# LLCC68.net
KiCad netlist of a schematic drawn in Altium Designer
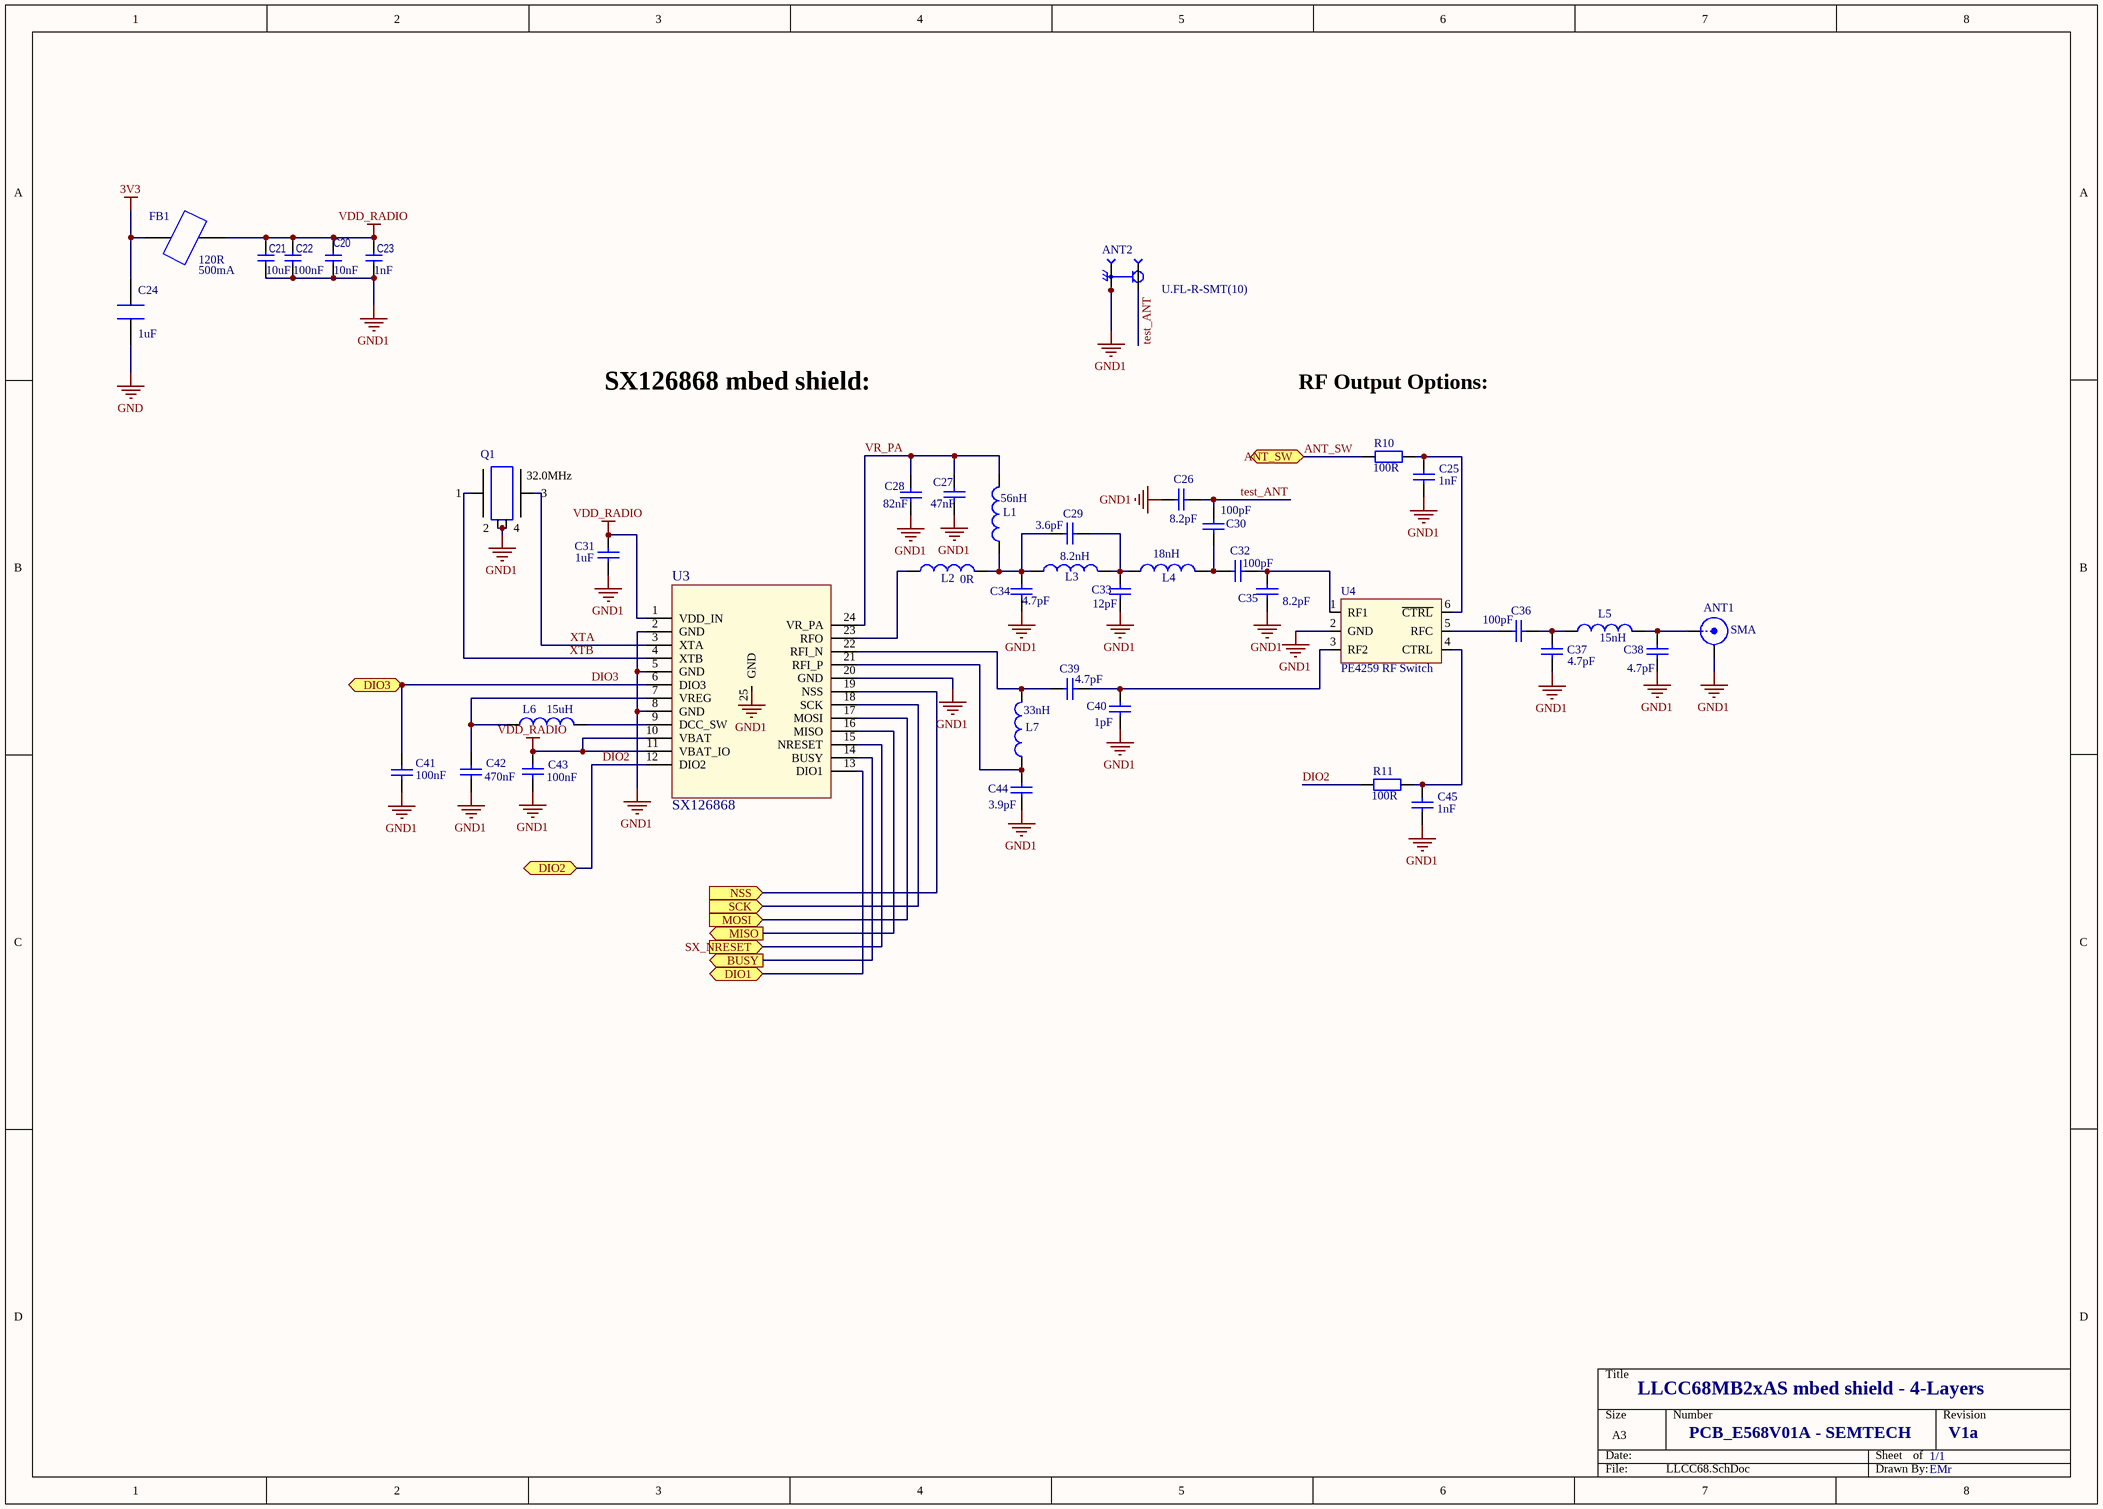
[diagram p0: LLCC68.SchDoc]

(export (version "E")
  (design (tool "Eeschema 10.0.6"))
  (components
    (comp (ref "ANT1")
      (value "SMA")
      (footprint "SMA_end_launch_1.0mm_9.52mm")
      (description "SMA Straight Connector")
      (fields (field (name "PUBLISHER") "Altium Limited"))
      (libsource (lib "SX1262MB2xAS_e499v01b") (part "SMA"))
    )
    (comp (ref "ANT2")
      (value "U.FL-R-SMT(10)")
      (footprint "HRS_U.FL-R-SMT(10)")
      (description "U.FL _UMCC_ Connector Receptacle, Male Pin 50Ohm Surface Mount Solder")
      (fields (field (name "MP") "U.FL-R-SMT_10_") (field (name "MF") "Hirose"))
      (libsource (lib "baseboard") (part "U.FL-R-SMT(10)"))
    )
    (comp (ref "C20")
      (value "10nF")
      (footprint "rlc_402_smd")
      (libsource (lib "baseboard") (part "ProE.tmp_22p_13"))
    )
    (comp (ref "C21")
      (value "10uF")
      (footprint "rlc_402_smd")
      (libsource (lib "baseboard") (part "ProE.tmp_22p_13"))
    )
    (comp (ref "C22")
      (value "100nF")
      (footprint "rlc_402_smd")
      (libsource (lib "baseboard") (part "ProE.tmp_22p_13"))
    )
    (comp (ref "C23")
      (value "1nF")
      (footprint "rlc_402_smd")
      (libsource (lib "baseboard") (part "ProE.tmp_22p_13"))
    )
    (comp (ref "C24")
      (value "1uF")
      (footprint "rlc_402_smd")
      (description "MLCC 4.7uF 0805 X5R 10V")
      (fields
        (field (name "XMOS PART NUMBER") "E-02-0021")
        (field (name "MANUFACTURER") "Murata")
        (field (name "PART CREATOR") "JG")
        (field (name "APPROVED") "NO")
      )
      (libsource (lib "XMOS_Alt_Lib") (part "CAP_NP"))
    )
    (comp (ref "C25")
      (value "1nF")
      (footprint "rlc_402_smd")
      (description "Capacitor SMD")
      (fields (field (name "PUBLISHER") "Altium Limited"))
      (libsource (lib "SX1262MB2xAS_e499v01b") (part "Cap"))
    )
    (comp (ref "C26")
      (value "8.2pF")
      (footprint "rlc_402_smd")
      (description "Capacitor SMD")
      (fields (field (name "PUBLISHER") "Altium Limited"))
      (libsource (lib "SX1262MB2xAS_e499v01b") (part "Cap"))
    )
    (comp (ref "C27")
      (value "47nF")
      (footprint "rlc_402_smd")
      (description "Capacitor SMD")
      (fields (field (name "PUBLISHER") "Altium Limited"))
      (libsource (lib "SX1262MB2xAS_e499v01b") (part "Cap"))
    )
    (comp (ref "C28")
      (value "82nF")
      (footprint "rlc_402_smd")
      (description "Capacitor SMD")
      (fields (field (name "PUBLISHER") "Altium Limited"))
      (libsource (lib "SX1262MB2xAS_e499v01b") (part "Cap"))
    )
    (comp (ref "C29")
      (value "3.6pF")
      (footprint "rlc_402_smd")
      (description "Capacitor SMD")
      (fields (field (name "PUBLISHER") "Altium Limited"))
      (libsource (lib "SX1262MB2xAS_e499v01b") (part "Cap"))
    )
    (comp (ref "C30")
      (value "100pF")
      (footprint "rlc_402_smd")
      (description "Capacitor SMD")
      (fields (field (name "PUBLISHER") "Altium Limited"))
      (libsource (lib "SX1262MB2xAS_e499v01b") (part "Cap"))
    )
    (comp (ref "C31")
      (value "1uF")
      (footprint "rlc_402_smd")
      (description "Capacitor SMD")
      (fields (field (name "PUBLISHER") "Altium Limited"))
      (libsource (lib "SX1262MB2xAS_e499v01b") (part "Cap"))
    )
    (comp (ref "C32")
      (value "100pF")
      (footprint "rlc_402_smd")
      (description "Capacitor SMD")
      (fields (field (name "PUBLISHER") "Altium Limited"))
      (libsource (lib "SX1262MB2xAS_e499v01b") (part "Cap"))
    )
    (comp (ref "C33")
      (value "12pF")
      (footprint "rlc_402_smd")
      (description "Capacitor SMD")
      (fields (field (name "PUBLISHER") "Altium Limited"))
      (libsource (lib "SX1262MB2xAS_e499v01b") (part "Cap"))
    )
    (comp (ref "C34")
      (value "4.7pF")
      (footprint "rlc_402_smd")
      (description "Capacitor SMD")
      (fields (field (name "PUBLISHER") "Altium Limited"))
      (libsource (lib "SX1262MB2xAS_e499v01b") (part "Cap"))
    )
    (comp (ref "C35")
      (value "8.2pF")
      (footprint "rlc_402_smd")
      (description "Capacitor SMD")
      (fields (field (name "PUBLISHER") "Altium Limited"))
      (libsource (lib "SX1262MB2xAS_e499v01b") (part "Cap"))
    )
    (comp (ref "C36")
      (value "100pF")
      (footprint "rlc_402_smd")
      (description "Capacitor SMD")
      (fields (field (name "PUBLISHER") "Altium Limited"))
      (libsource (lib "SX1262MB2xAS_e499v01b") (part "Cap"))
    )
    (comp (ref "C37")
      (value "4.7pF")
      (footprint "rlc_402_smd")
      (description "Capacitor SMD")
      (fields (field (name "PUBLISHER") "Altium Limited"))
      (libsource (lib "SX1262MB2xAS_e499v01b") (part "Cap"))
    )
    (comp (ref "C38")
      (value "4.7pF")
      (footprint "rlc_402_smd")
      (description "Capacitor SMD")
      (fields (field (name "PUBLISHER") "Altium Limited"))
      (libsource (lib "SX1262MB2xAS_e499v01b") (part "Cap"))
    )
    (comp (ref "C39")
      (value "4.7pF")
      (footprint "rlc_402_smd")
      (description "Capacitor SMD")
      (fields (field (name "PUBLISHER") "Altium Limited"))
      (libsource (lib "SX1262MB2xAS_e499v01b") (part "Cap"))
    )
    (comp (ref "C40")
      (value "1pF")
      (footprint "rlc_402_smd")
      (description "Capacitor SMD")
      (fields (field (name "PUBLISHER") "Altium Limited"))
      (libsource (lib "SX1262MB2xAS_e499v01b") (part "Cap"))
    )
    (comp (ref "C41")
      (value "100nF")
      (footprint "rlc_402_smd")
      (description "Capacitor SMD")
      (fields (field (name "PUBLISHER") "Altium Limited"))
      (libsource (lib "LLCC68MB2xAS_e568v01a") (part "Cap"))
    )
    (comp (ref "C42")
      (value "470nF")
      (footprint "rlc_402_smd")
      (description "Capacitor SMD")
      (fields (field (name "PUBLISHER") "Altium Limited"))
      (libsource (lib "SX1262MB2xAS_e499v01b") (part "Cap"))
    )
    (comp (ref "C43")
      (value "100nF")
      (footprint "rlc_402_smd")
      (description "Capacitor SMD")
      (fields (field (name "PUBLISHER") "Altium Limited"))
      (libsource (lib "SX1262MB2xAS_e499v01b") (part "Cap"))
    )
    (comp (ref "C44")
      (value "3.9pF")
      (footprint "rlc_402_smd")
      (description "Capacitor SMD")
      (fields (field (name "PUBLISHER") "Altium Limited"))
      (libsource (lib "SX1262MB2xAS_e499v01b") (part "Cap"))
    )
    (comp (ref "C45")
      (value "1nF")
      (footprint "rlc_402_smd")
      (description "Capacitor SMD")
      (fields (field (name "PUBLISHER") "Altium Limited"))
      (libsource (lib "SX1262MB2xAS_e499v01b") (part "Cap"))
    )
    (comp (ref "FB1")
      (value "120R")
      (footprint "R0603")
      (description "Ferrite Bead, 120R AT 100MHz, 0603, 500mA")
      (fields
        (field (name "XMOS PART NUMBER") "E-08-0007")
        (field (name "RATED CURRENT") "500mA")
        (field (name "MANUFACTURER") "Murata")
        (field (name "PART CREATOR") "JG")
        (field (name "APPROVED") "NO")
      )
      (libsource (lib "XMOS_Alt_Lib") (part "FERRITE"))
    )
    (comp (ref "L1")
      (value "56nH")
      (footprint "rlc_402_smd")
      (description "Inductor SMD")
      (fields (field (name "PUBLISHER") "Altium Limited"))
      (libsource (lib "SX1262MB2xAS_e499v01b") (part "Inductor"))
    )
    (comp (ref "L2")
      (value "0R")
      (footprint "rlc_402_smd")
      (description "Inductor SMD")
      (fields (field (name "PUBLISHER") "Altium Limited"))
      (libsource (lib "SX1262MB2xAS_e499v01b") (part "Inductor"))
    )
    (comp (ref "L3")
      (value "8.2nH")
      (footprint "rlc_402_smd")
      (description "Inductor SMD")
      (fields (field (name "PUBLISHER") "Altium Limited"))
      (libsource (lib "SX1262MB2xAS_e499v01b") (part "Inductor"))
    )
    (comp (ref "L4")
      (value "18nH")
      (footprint "rlc_402_smd")
      (description "Inductor SMD")
      (fields (field (name "PUBLISHER") "Altium Limited"))
      (libsource (lib "SX1262MB2xAS_e499v01b") (part "Inductor"))
    )
    (comp (ref "L5")
      (value "15nH")
      (footprint "rlc_402_smd")
      (description "Inductor SMD")
      (fields (field (name "PUBLISHER") "Altium Limited"))
      (libsource (lib "SX1262MB2xAS_e499v01b") (part "Inductor"))
    )
    (comp (ref "L6")
      (value "15uH")
      (footprint "rlc_805_smd enlarged")
      (description "Inductor SMD")
      (fields (field (name "PUBLISHER") "Altium Limited"))
      (libsource (lib "SX1262MB2xAS_e499v01b") (part "Inductor"))
    )
    (comp (ref "L7")
      (value "33nH")
      (footprint "rlc_402_smd")
      (description "Inductor SMD")
      (fields (field (name "PUBLISHER") "Altium Limited"))
      (libsource (lib "SX1262MB2xAS_e499v01b") (part "Inductor"))
    )
    (comp (ref "Q1")
      (value "32.0MHz")
      (footprint "nd2016da")
      (description "Crystal with GND pins")
      (fields (field (name "Comment") "32MHz"))
      (libsource (lib "SX1262MB2xAS_e499v01b") (part "Xtal GND"))
    )
    (comp (ref "R10")
      (value "100R")
      (footprint "rlc_402_smd")
      (description "Resistor SMD - IEC symbol version")
      (libsource (lib "SX1262MB2xAS_e499v01b") (part "Resistor"))
    )
    (comp (ref "R11")
      (value "100R")
      (footprint "rlc_402_smd")
      (description "Resistor SMD - IEC symbol version")
      (libsource (lib "SX1262MB2xAS_e499v01b") (part "Resistor"))
    )
    (comp (ref "U3")
      (value "SX126868")
      (footprint "vqfn24_4x4mm")
      (description "SX1262- Ultra low power RF transceiver")
      (libsource (lib "SX1262MB2xAS_e499v01b") (part "SX126x"))
    )
    (comp (ref "U4")
      (value "PE4259 RF Switch")
      (footprint "SC70-6")
      (description "PE4259 Peregrine RF Switch")
      (libsource (lib "SX1262MB2xAS_e499v01b") (part "PE4259 RF Switch"))
    )
  )
  (nets
    (net (code "1") (name "/ANT_SW") (class "Default")
      (node (ref "R10") (pin "2") (pinfunction "2_2") (pintype "passive"))
    )
    (net (code "2") (name "/BUSY") (class "Default")
      (node (ref "U3") (pin "14") (pinfunction "BUSY_14") (pintype "passive"))
    )
    (net (code "3") (name "/DIO1") (class "Default")
      (node (ref "U3") (pin "13") (pinfunction "DIO1_13") (pintype "passive"))
    )
    (net (code "4") (name "/DIO2") (class "Default")
      (node (ref "R11") (pin "2") (pinfunction "2_2") (pintype "passive"))
      (node (ref "U3") (pin "12") (pinfunction "DIO2_12") (pintype "passive"))
    )
    (net (code "5") (name "/DIO3") (class "Default")
      (node (ref "C41") (pin "2") (pinfunction "2_2") (pintype "passive"))
      (node (ref "U3") (pin "6") (pinfunction "DIO3_6") (pintype "passive"))
    )
    (net (code "6") (name "/MISO") (class "Default")
      (node (ref "U3") (pin "16") (pinfunction "MISO_16") (pintype "passive"))
    )
    (net (code "7") (name "/MOSI") (class "Default")
      (node (ref "U3") (pin "17") (pinfunction "MOSI_17") (pintype "passive"))
    )
    (net (code "8") (name "/NSS") (class "Default")
      (node (ref "U3") (pin "19") (pinfunction "NSS_19") (pintype "passive"))
    )
    (net (code "9") (name "/SCK") (class "Default")
      (node (ref "U3") (pin "18") (pinfunction "SCK_18") (pintype "passive"))
    )
    (net (code "10") (name "/SX_NRESET") (class "Default")
      (node (ref "U3") (pin "15") (pinfunction "NRESET_15") (pintype "passive"))
    )
    (net (code "11") (name "/VR_PA") (class "Default")
      (node (ref "C27") (pin "2") (pinfunction "2_2") (pintype "passive"))
      (node (ref "C28") (pin "2") (pinfunction "2_2") (pintype "passive"))
      (node (ref "L1") (pin "2") (pinfunction "2_2") (pintype "passive"))
      (node (ref "U3") (pin "24") (pinfunction "VR_PA_24") (pintype "power_in"))
    )
    (net (code "12") (name "/XTA") (class "Default")
      (node (ref "Q1") (pin "3") (pinfunction "3_3") (pintype "passive"))
      (node (ref "U3") (pin "3") (pinfunction "XTA_3") (pintype "passive"))
    )
    (net (code "14") (name "/XTB") (class "Default")
      (node (ref "Q1") (pin "1") (pinfunction "1_1") (pintype "passive"))
      (node (ref "U3") (pin "4") (pinfunction "XTB_4") (pintype "passive"))
    )
    (net (code "15") (name "/test_ANT") (class "Default")
      (node (ref "ANT2") (pin "1") (pinfunction "SIG_1") (pintype "passive"))
      (node (ref "C26") (pin "2") (pinfunction "2_2") (pintype "passive"))
      (node (ref "C30") (pin "1") (pinfunction "1_1") (pintype "passive"))
    )
    (net (code "16") (name "3V3") (class "Default")
      (node (ref "C24") (pin "1") (pinfunction "T1_1") (pintype "passive"))
      (node (ref "FB1") (pin "1") (pinfunction "P1_1") (pintype "passive"))
    )
    (net (code "17") (name "GND") (class "Default")
      (node (ref "C24") (pin "2") (pinfunction "T2_2") (pintype "passive"))
    )
    (net (code "18") (name "GND1") (class "Default")
      (node (ref "ANT1") (pin "2") (pinfunction "GND_2") (pintype "passive"))
      (node (ref "ANT2") (pin "2") (pinfunction "GND_2") (pintype "passive"))
      (node (ref "ANT2") (pin "3") (pinfunction "GND_3") (pintype "passive"))
      (node (ref "C20") (pin "2") (pintype "passive"))
      (node (ref "C21") (pin "2") (pintype "passive"))
      (node (ref "C22") (pin "2") (pintype "passive"))
      (node (ref "C23") (pin "2") (pintype "passive"))
      (node (ref "C25") (pin "2") (pinfunction "2_2") (pintype "passive"))
      (node (ref "C26") (pin "1") (pinfunction "1_1") (pintype "passive"))
      (node (ref "C27") (pin "1") (pinfunction "1_1") (pintype "passive"))
      (node (ref "C28") (pin "1") (pinfunction "1_1") (pintype "passive"))
      (node (ref "C31") (pin "1") (pinfunction "1_1") (pintype "passive"))
      (node (ref "C33") (pin "1") (pinfunction "1_1") (pintype "passive"))
      (node (ref "C34") (pin "1") (pinfunction "1_1") (pintype "passive"))
      (node (ref "C35") (pin "1") (pinfunction "1_1") (pintype "passive"))
      (node (ref "C37") (pin "1") (pinfunction "1_1") (pintype "passive"))
      (node (ref "C38") (pin "1") (pinfunction "1_1") (pintype "passive"))
      (node (ref "C40") (pin "1") (pinfunction "1_1") (pintype "passive"))
      (node (ref "C41") (pin "1") (pinfunction "1_1") (pintype "passive"))
      (node (ref "C42") (pin "1") (pinfunction "1_1") (pintype "passive"))
      (node (ref "C43") (pin "1") (pinfunction "1_1") (pintype "passive"))
      (node (ref "C44") (pin "1") (pinfunction "1_1") (pintype "passive"))
      (node (ref "C45") (pin "2") (pinfunction "2_2") (pintype "passive"))
      (node (ref "Q1") (pin "2") (pinfunction "2_2") (pintype "passive"))
      (node (ref "Q1") (pin "4") (pinfunction "4_4") (pintype "passive"))
      (node (ref "U3") (pin "2") (pinfunction "GND_2") (pintype "passive"))
      (node (ref "U3") (pin "20") (pinfunction "GND_20") (pintype "passive"))
      (node (ref "U3") (pin "25") (pinfunction "GND_25") (pintype "passive"))
      (node (ref "U3") (pin "5") (pinfunction "GND_5") (pintype "passive"))
      (node (ref "U3") (pin "8") (pinfunction "GND_8") (pintype "passive"))
      (node (ref "U4") (pin "2") (pinfunction "GND_2") (pintype "passive"))
    )
    (net (code "19") (name "Net-(ANT1-Signal)") (class "Default")
      (node (ref "ANT1") (pin "1") (pinfunction "Signal_1") (pintype "passive"))
      (node (ref "C38") (pin "2") (pinfunction "2_2") (pintype "passive"))
      (node (ref "L5") (pin "2") (pinfunction "2_2") (pintype "passive"))
    )
    (net (code "20") (name "Net-(C29-Pad1)") (class "Default")
      (node (ref "C29") (pin "1") (pinfunction "1_1") (pintype "passive"))
      (node (ref "C33") (pin "2") (pinfunction "2_2") (pintype "passive"))
      (node (ref "L3") (pin "2") (pinfunction "2_2") (pintype "passive"))
      (node (ref "L4") (pin "1") (pinfunction "1_1") (pintype "passive"))
    )
    (net (code "21") (name "Net-(C29-Pad2)") (class "Default")
      (node (ref "C29") (pin "2") (pinfunction "2_2") (pintype "passive"))
      (node (ref "C34") (pin "2") (pinfunction "2_2") (pintype "passive"))
      (node (ref "L1") (pin "1") (pinfunction "1_1") (pintype "passive"))
      (node (ref "L2") (pin "2") (pinfunction "2_2") (pintype "passive"))
      (node (ref "L3") (pin "1") (pinfunction "1_1") (pintype "passive"))
    )
    (net (code "22") (name "Net-(C30-Pad2)") (class "Default")
      (node (ref "C30") (pin "2") (pinfunction "2_2") (pintype "passive"))
      (node (ref "C32") (pin "2") (pinfunction "2_2") (pintype "passive"))
      (node (ref "L4") (pin "2") (pinfunction "2_2") (pintype "passive"))
    )
    (net (code "23") (name "Net-(C36-Pad1)") (class "Default")
      (node (ref "C36") (pin "1") (pinfunction "1_1") (pintype "passive"))
      (node (ref "C37") (pin "2") (pinfunction "2_2") (pintype "passive"))
      (node (ref "L5") (pin "1") (pinfunction "1_1") (pintype "passive"))
    )
    (net (code "24") (name "Net-(U3-DCC_SW)") (class "Default")
      (node (ref "L6") (pin "2") (pinfunction "2_2") (pintype "passive"))
      (node (ref "U3") (pin "9") (pinfunction "DCC_SW_9") (pintype "power_in"))
    )
    (net (code "25") (name "Net-(U3-RFI_N)") (class "Default")
      (node (ref "C39") (pin "2") (pinfunction "2_2") (pintype "passive"))
      (node (ref "L7") (pin "2") (pinfunction "2_2") (pintype "passive"))
      (node (ref "U3") (pin "22") (pinfunction "RFI_N_22") (pintype "passive"))
    )
    (net (code "26") (name "Net-(U3-RFI_P)") (class "Default")
      (node (ref "C44") (pin "2") (pinfunction "2_2") (pintype "passive"))
      (node (ref "L7") (pin "1") (pinfunction "1_1") (pintype "passive"))
      (node (ref "U3") (pin "21") (pinfunction "RFI_P_21") (pintype "passive"))
    )
    (net (code "27") (name "Net-(U3-RFO)") (class "Default")
      (node (ref "L2") (pin "1") (pinfunction "1_1") (pintype "passive"))
      (node (ref "U3") (pin "23") (pinfunction "RFO_23") (pintype "passive"))
    )
    (net (code "28") (name "Net-(U3-VREG)") (class "Default")
      (node (ref "C42") (pin "2") (pinfunction "2_2") (pintype "passive"))
      (node (ref "L6") (pin "1") (pinfunction "1_1") (pintype "passive"))
      (node (ref "U3") (pin "7") (pinfunction "VREG_7") (pintype "power_in"))
    )
    (net (code "29") (name "Net-(U4-CTRL)") (class "Default")
      (node (ref "C45") (pin "1") (pinfunction "1_1") (pintype "passive"))
      (node (ref "R11") (pin "1") (pinfunction "1_1") (pintype "passive"))
      (node (ref "U4") (pin "4") (pinfunction "CTRL_4") (pintype "passive"))
    )
    (net (code "30") (name "Net-(U4-RF1)") (class "Default")
      (node (ref "C32") (pin "1") (pinfunction "1_1") (pintype "passive"))
      (node (ref "C35") (pin "2") (pinfunction "2_2") (pintype "passive"))
      (node (ref "U4") (pin "1") (pinfunction "RF1_1") (pintype "passive"))
    )
    (net (code "31") (name "Net-(U4-RF2)") (class "Default")
      (node (ref "C39") (pin "1") (pinfunction "1_1") (pintype "passive"))
      (node (ref "C40") (pin "2") (pinfunction "2_2") (pintype "passive"))
      (node (ref "U4") (pin "3") (pinfunction "RF2_3") (pintype "passive"))
    )
    (net (code "32") (name "Net-(U4-RFC)") (class "Default")
      (node (ref "C36") (pin "2") (pinfunction "2_2") (pintype "passive"))
      (node (ref "U4") (pin "5") (pinfunction "RFC_5") (pintype "passive"))
    )
    (net (code "33") (name "Net-(U4-~{CTRL})") (class "Default")
      (node (ref "C25") (pin "1") (pinfunction "1_1") (pintype "passive"))
      (node (ref "R10") (pin "1") (pinfunction "1_1") (pintype "passive"))
      (node (ref "U4") (pin "6") (pinfunction "~{CTRL}_6") (pintype "passive"))
    )
    (net (code "34") (name "VDD_RADIO") (class "Default")
      (node (ref "C20") (pin "1") (pintype "passive"))
      (node (ref "C21") (pin "1") (pintype "passive"))
      (node (ref "C22") (pin "1") (pintype "passive"))
      (node (ref "C23") (pin "1") (pintype "passive"))
      (node (ref "C31") (pin "2") (pinfunction "2_2") (pintype "passive"))
      (node (ref "C43") (pin "2") (pinfunction "2_2") (pintype "passive"))
      (node (ref "FB1") (pin "2") (pinfunction "P2_2") (pintype "passive"))
      (node (ref "U3") (pin "1") (pinfunction "VDD_IN_1") (pintype "power_in"))
      (node (ref "U3") (pin "10") (pinfunction "VBAT_10") (pintype "power_in"))
      (node (ref "U3") (pin "11") (pinfunction "VBAT_IO_11") (pintype "power_in"))
    )
  )
)
